# ATOL_MAIN_BOARD_R02A03_20191009.net
KiCad netlist of a schematic drawn in Altium Designer
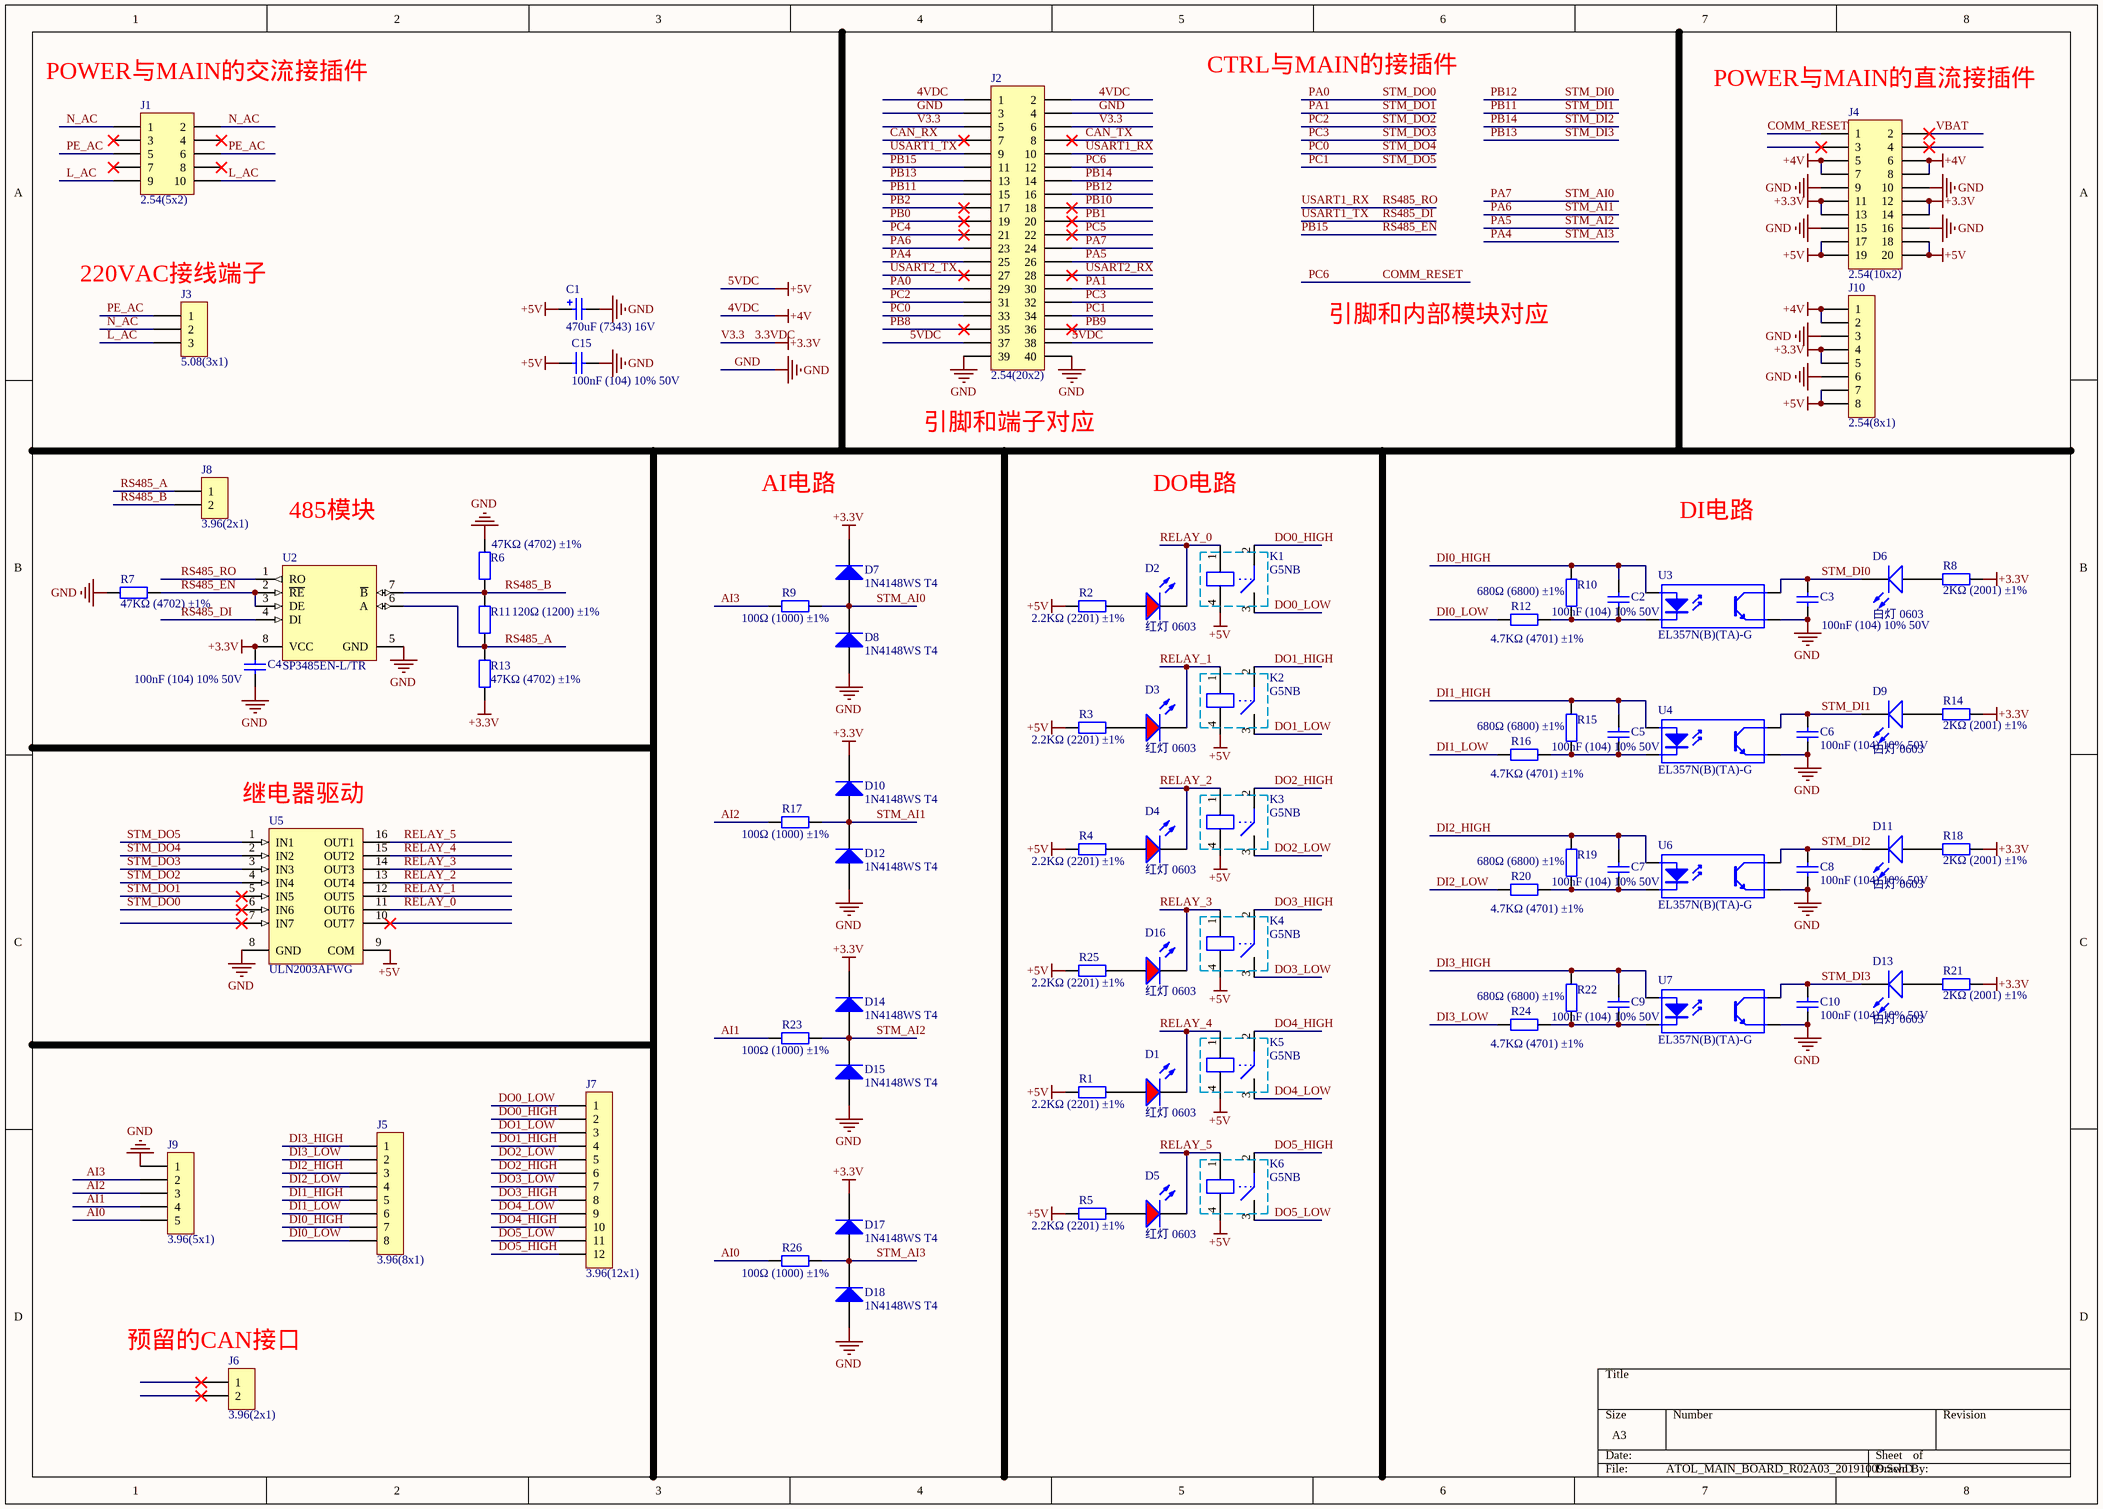
[diagram p0: ATOL_MAIN_BOARD_R02A03_20191009.SchDoc]

(export (version "E")
  (design (tool "Eeschema 10.0.6"))
  (components
    (comp (ref "C1")
      (value "470uF (7343) 16V")
      (footprint "STEC_E(7343-43)")
      (description "钽电容")
      (libsource (lib "Miscellaneous Devices LC") (part "3528 100uF (107) 10% 6.3V"))
    )
    (comp (ref "C2")
      (value "100nF (104) 10% 50V")
      (footprint "0603_C")
      (description "贴片电容")
      (libsource (lib "Miscellaneous Devices LC") (part "0603 100nF (104) 10% 50V"))
    )
    (comp (ref "C3")
      (value "100nF (104) 10% 50V")
      (footprint "0603_C")
      (description "贴片电容")
      (libsource (lib "Miscellaneous Devices LC") (part "0603 100nF (104) 10% 50V"))
    )
    (comp (ref "C4")
      (value "100nF (104) 10% 50V")
      (footprint "0603_C")
      (description "贴片电容")
      (libsource (lib "Miscellaneous Devices LC") (part "0603 100nF (104) 10% 50V"))
    )
    (comp (ref "C5")
      (value "100nF (104) 10% 50V")
      (footprint "0603_C")
      (description "贴片电容")
      (libsource (lib "Miscellaneous Devices LC") (part "0603 100nF (104) 10% 50V"))
    )
    (comp (ref "C6")
      (value "100nF (104) 10% 50V")
      (footprint "0603_C")
      (description "贴片电容")
      (libsource (lib "Miscellaneous Devices LC") (part "0603 100nF (104) 10% 50V"))
    )
    (comp (ref "C7")
      (value "100nF (104) 10% 50V")
      (footprint "0603_C")
      (description "贴片电容")
      (libsource (lib "Miscellaneous Devices LC") (part "0603 100nF (104) 10% 50V"))
    )
    (comp (ref "C8")
      (value "100nF (104) 10% 50V")
      (footprint "0603_C")
      (description "贴片电容")
      (libsource (lib "Miscellaneous Devices LC") (part "0603 100nF (104) 10% 50V"))
    )
    (comp (ref "C9")
      (value "100nF (104) 10% 50V")
      (footprint "0603_C")
      (description "贴片电容")
      (libsource (lib "Miscellaneous Devices LC") (part "0603 100nF (104) 10% 50V"))
    )
    (comp (ref "C10")
      (value "100nF (104) 10% 50V")
      (footprint "0603_C")
      (description "贴片电容")
      (libsource (lib "Miscellaneous Devices LC") (part "0603 100nF (104) 10% 50V"))
    )
    (comp (ref "C15")
      (value "100nF (104) 10% 50V")
      (footprint "0603_C")
      (description "贴片电容")
      (libsource (lib "Miscellaneous Devices LC") (part "0603 100nF (104) 10% 50V"))
    )
    (comp (ref "D1")
      (value "红灯 0603")
      (footprint "0603_LED_S1")
      (description "发光二极管")
      (libsource (lib "Miscellaneous Devices LC") (part "0603 红灯"))
    )
    (comp (ref "D2")
      (value "红灯 0603")
      (footprint "0603_LED_S1")
      (description "发光二极管")
      (libsource (lib "Miscellaneous Devices LC") (part "0603 红灯"))
    )
    (comp (ref "D3")
      (value "红灯 0603")
      (footprint "0603_LED_S1")
      (description "发光二极管")
      (libsource (lib "Miscellaneous Devices LC") (part "0603 红灯"))
    )
    (comp (ref "D4")
      (value "红灯 0603")
      (footprint "0603_LED_S1")
      (description "发光二极管")
      (libsource (lib "Miscellaneous Devices LC") (part "0603 红灯"))
    )
    (comp (ref "D5")
      (value "红灯 0603")
      (footprint "0603_LED_S1")
      (description "发光二极管")
      (libsource (lib "Miscellaneous Devices LC") (part "0603 红灯"))
    )
    (comp (ref "D6")
      (value "白灯 0603")
      (footprint "0603_LED_S1")
      (description "发光二极管")
      (libsource (lib "Miscellaneous Devices LC") (part "0603 白灯"))
    )
    (comp (ref "D7")
      (value "1N4148WS T4")
      (footprint "SOD-323")
      (description "二极管")
      (libsource (lib "Miscellaneous Devices LC") (part "SOD-323 1N4148WS T4"))
    )
    (comp (ref "D8")
      (value "1N4148WS T4")
      (footprint "SOD-323")
      (description "二极管")
      (libsource (lib "Miscellaneous Devices LC") (part "SOD-323 1N4148WS T4"))
    )
    (comp (ref "D9")
      (value "白灯 0603")
      (footprint "0603_LED_S1")
      (description "发光二极管")
      (libsource (lib "Miscellaneous Devices LC") (part "0603 白灯"))
    )
    (comp (ref "D10")
      (value "1N4148WS T4")
      (footprint "SOD-323")
      (description "二极管")
      (libsource (lib "Miscellaneous Devices LC") (part "SOD-323 1N4148WS T4"))
    )
    (comp (ref "D11")
      (value "白灯 0603")
      (footprint "0603_LED_S1")
      (description "发光二极管")
      (libsource (lib "Miscellaneous Devices LC") (part "0603 白灯"))
    )
    (comp (ref "D12")
      (value "1N4148WS T4")
      (footprint "SOD-323")
      (description "二极管")
      (libsource (lib "Miscellaneous Devices LC") (part "SOD-323 1N4148WS T4"))
    )
    (comp (ref "D13")
      (value "白灯 0603")
      (footprint "0603_LED_S1")
      (description "发光二极管")
      (libsource (lib "Miscellaneous Devices LC") (part "0603 白灯"))
    )
    (comp (ref "D14")
      (value "1N4148WS T4")
      (footprint "SOD-323")
      (description "二极管")
      (libsource (lib "Miscellaneous Devices LC") (part "SOD-323 1N4148WS T4"))
    )
    (comp (ref "D15")
      (value "1N4148WS T4")
      (footprint "SOD-323")
      (description "二极管")
      (libsource (lib "Miscellaneous Devices LC") (part "SOD-323 1N4148WS T4"))
    )
    (comp (ref "D16")
      (value "红灯 0603")
      (footprint "0603_LED_S1")
      (description "发光二极管")
      (libsource (lib "Miscellaneous Devices LC") (part "0603 红灯"))
    )
    (comp (ref "D17")
      (value "1N4148WS T4")
      (footprint "SOD-323")
      (description "二极管")
      (libsource (lib "Miscellaneous Devices LC") (part "SOD-323 1N4148WS T4"))
    )
    (comp (ref "D18")
      (value "1N4148WS T4")
      (footprint "SOD-323")
      (description "二极管")
      (libsource (lib "Miscellaneous Devices LC") (part "SOD-323 1N4148WS T4"))
    )
    (comp (ref "J1")
      (value "2.54(5x2)")
      (footprint "DB2.54(5x2)")
      (description "2.54端子")
      (libsource (lib "connector") (part "2.54(5x2)"))
    )
    (comp (ref "J2")
      (value "2.54(20x2)")
      (footprint "DB2.54(20x2)")
      (description "2.54端子")
      (libsource (lib "connector") (part "2.54(20x2)"))
    )
    (comp (ref "J3")
      (value "5.08(3x1)")
      (footprint "KF2EDGK5.08-WI-3P")
      (description "5.08端子")
      (libsource (lib "connector") (part "5.08(3x1)"))
    )
    (comp (ref "J4")
      (value "2.54(10x2)")
      (footprint "DB2.54(10x2)")
      (description "2.54端子")
      (libsource (lib "connector") (part "2.54(10x2)"))
    )
    (comp (ref "J5")
      (value "3.96(8x1)")
      (footprint "HT3.96-WI-8P")
      (description "3.96端子")
      (libsource (lib "connector") (part "3.96(8x1)"))
    )
    (comp (ref "J6")
      (value "3.96(2x1)")
      (footprint "HT3.96-WI-2P")
      (description "3.96端子")
      (libsource (lib "connector") (part "3.96(2x1)"))
    )
    (comp (ref "J7")
      (value "3.96(12x1)")
      (footprint "HT3.96-WI-12P")
      (description "3.96端子")
      (libsource (lib "connector") (part "3.96(12x1)"))
    )
    (comp (ref "J8")
      (value "3.96(2x1)")
      (footprint "HT3.96-WI-2P")
      (description "3.96端子")
      (libsource (lib "connector") (part "3.96(2x1)"))
    )
    (comp (ref "J9")
      (value "3.96(5x1)")
      (footprint "HT3.96-WI-5P")
      (description "3.96端子")
      (libsource (lib "connector") (part "3.96(5x1)"))
    )
    (comp (ref "J10")
      (value "2.54(8x1)")
      (footprint "DB2.54(8x1)")
      (description "2.54端子")
      (libsource (lib "connector") (part "2.54(8x1)"))
    )
    (comp (ref "K1")
      (value "G5NB")
      (footprint "G5NG")
      (description "G5NB/12V/16mA/720R")
      (libsource (lib "ATOL_CHIP") (part "G5NB"))
    )
    (comp (ref "K2")
      (value "G5NB")
      (footprint "G5NG")
      (description "G5NB/12V/16mA/720R")
      (libsource (lib "ATOL_CHIP") (part "G5NB"))
    )
    (comp (ref "K3")
      (value "G5NB")
      (footprint "G5NG")
      (description "G5NB/12V/16mA/720R")
      (libsource (lib "ATOL_CHIP") (part "G5NB"))
    )
    (comp (ref "K4")
      (value "G5NB")
      (footprint "G5NG")
      (description "G5NB/12V/16mA/720R")
      (libsource (lib "ATOL_CHIP") (part "G5NB"))
    )
    (comp (ref "K5")
      (value "G5NB")
      (footprint "G5NG")
      (description "G5NB/12V/16mA/720R")
      (libsource (lib "ATOL_CHIP") (part "G5NB"))
    )
    (comp (ref "K6")
      (value "G5NB")
      (footprint "G5NG")
      (description "G5NB/12V/16mA/720R")
      (libsource (lib "ATOL_CHIP") (part "G5NB"))
    )
    (comp (ref "R1")
      (value "2.2KΩ (2201) ±1%")
      (footprint "0603_R")
      (description "贴片电阻")
      (libsource (lib "Miscellaneous Devices LC") (part "0603 2.2KΩ (2201) 1%"))
    )
    (comp (ref "R2")
      (value "2.2KΩ (2201) ±1%")
      (footprint "0603_R")
      (description "贴片电阻")
      (libsource (lib "Miscellaneous Devices LC") (part "0603 2.2KΩ (2201) 1%"))
    )
    (comp (ref "R3")
      (value "2.2KΩ (2201) ±1%")
      (footprint "0603_R")
      (description "贴片电阻")
      (libsource (lib "Miscellaneous Devices LC") (part "0603 2.2KΩ (2201) 1%"))
    )
    (comp (ref "R4")
      (value "2.2KΩ (2201) ±1%")
      (footprint "0603_R")
      (description "贴片电阻")
      (libsource (lib "Miscellaneous Devices LC") (part "0603 2.2KΩ (2201) 1%"))
    )
    (comp (ref "R5")
      (value "2.2KΩ (2201) ±1%")
      (footprint "0603_R")
      (description "贴片电阻")
      (libsource (lib "Miscellaneous Devices LC") (part "0603 2.2KΩ (2201) 1%"))
    )
    (comp (ref "R6")
      (value "47KΩ (4702) ±1%")
      (footprint "0603_R")
      (description "贴片电阻")
      (libsource (lib "Miscellaneous Devices LC") (part "0603 47KΩ (4702) 1%"))
    )
    (comp (ref "R7")
      (value "47KΩ (4702) ±1%")
      (footprint "0603_R")
      (description "贴片电阻")
      (libsource (lib "") (part "0603 47KΩ (4702) 1%_1"))
    )
    (comp (ref "R8")
      (value "2KΩ (2001) ±1%")
      (footprint "0603_R")
      (description "贴片电阻")
      (libsource (lib "Miscellaneous Devices LC") (part "0603 2KΩ (2001) 1%"))
    )
    (comp (ref "R9")
      (value "100Ω (1000) ±1%")
      (footprint "0603_R")
      (description "贴片电阻")
      (libsource (lib "Miscellaneous Devices LC") (part "0603 100Ω (1000) 1%"))
    )
    (comp (ref "R10")
      (value "680Ω (6800) ±1%")
      (footprint "0603_R")
      (description "贴片电阻")
      (libsource (lib "Miscellaneous Devices LC") (part "0603 680Ω (6800) 1%"))
    )
    (comp (ref "R11")
      (value "120Ω (1200) ±1%")
      (footprint "0603_R")
      (description "贴片电阻")
      (libsource (lib "Miscellaneous Devices LC") (part "0603 120Ω (1200) 1%"))
    )
    (comp (ref "R12")
      (value "4.7KΩ (4701) ±1%")
      (footprint "0603_R")
      (description "贴片电阻")
      (libsource (lib "Miscellaneous Devices LC") (part "0603 4.7KΩ (4701) 1%"))
    )
    (comp (ref "R13")
      (value "47KΩ (4702) ±1%")
      (footprint "0603_R")
      (description "贴片电阻")
      (libsource (lib "Miscellaneous Devices LC") (part "0603 47KΩ (4702) 1%"))
    )
    (comp (ref "R14")
      (value "2KΩ (2001) ±1%")
      (footprint "0603_R")
      (description "贴片电阻")
      (libsource (lib "Miscellaneous Devices LC") (part "0603 2KΩ (2001) 1%"))
    )
    (comp (ref "R15")
      (value "680Ω (6800) ±1%")
      (footprint "0603_R")
      (description "贴片电阻")
      (libsource (lib "Miscellaneous Devices LC") (part "0603 680Ω (6800) 1%"))
    )
    (comp (ref "R16")
      (value "4.7KΩ (4701) ±1%")
      (footprint "0603_R")
      (description "贴片电阻")
      (libsource (lib "Miscellaneous Devices LC") (part "0603 4.7KΩ (4701) 1%"))
    )
    (comp (ref "R17")
      (value "100Ω (1000) ±1%")
      (footprint "0603_R")
      (description "贴片电阻")
      (libsource (lib "Miscellaneous Devices LC") (part "0603 100Ω (1000) 1%"))
    )
    (comp (ref "R18")
      (value "2KΩ (2001) ±1%")
      (footprint "0603_R")
      (description "贴片电阻")
      (libsource (lib "Miscellaneous Devices LC") (part "0603 2KΩ (2001) 1%"))
    )
    (comp (ref "R19")
      (value "680Ω (6800) ±1%")
      (footprint "0603_R")
      (description "贴片电阻")
      (libsource (lib "Miscellaneous Devices LC") (part "0603 680Ω (6800) 1%"))
    )
    (comp (ref "R20")
      (value "4.7KΩ (4701) ±1%")
      (footprint "0603_R")
      (description "贴片电阻")
      (libsource (lib "Miscellaneous Devices LC") (part "0603 4.7KΩ (4701) 1%"))
    )
    (comp (ref "R21")
      (value "2KΩ (2001) ±1%")
      (footprint "0603_R")
      (description "贴片电阻")
      (libsource (lib "Miscellaneous Devices LC") (part "0603 2KΩ (2001) 1%"))
    )
    (comp (ref "R22")
      (value "680Ω (6800) ±1%")
      (footprint "0603_R")
      (description "贴片电阻")
      (libsource (lib "Miscellaneous Devices LC") (part "0603 680Ω (6800) 1%"))
    )
    (comp (ref "R23")
      (value "100Ω (1000) ±1%")
      (footprint "0603_R")
      (description "贴片电阻")
      (libsource (lib "Miscellaneous Devices LC") (part "0603 100Ω (1000) 1%"))
    )
    (comp (ref "R24")
      (value "4.7KΩ (4701) ±1%")
      (footprint "0603_R")
      (description "贴片电阻")
      (libsource (lib "Miscellaneous Devices LC") (part "0603 4.7KΩ (4701) 1%"))
    )
    (comp (ref "R25")
      (value "2.2KΩ (2201) ±1%")
      (footprint "0603_R")
      (description "贴片电阻")
      (libsource (lib "Miscellaneous Devices LC") (part "0603 2.2KΩ (2201) 1%"))
    )
    (comp (ref "R26")
      (value "100Ω (1000) ±1%")
      (footprint "0603_R")
      (description "贴片电阻")
      (libsource (lib "Miscellaneous Devices LC") (part "0603 100Ω (1000) 1%"))
    )
    (comp (ref "U2")
      (value "SP3485EN-L/TR")
      (footprint "SOIC-8_150mil")
      (description "RS-485/RS-422")
      (libsource (lib "Miscellaneous Devices LC") (part "SP3485EN-L/TR_[C8963]"))
    )
    (comp (ref "U3")
      (value "EL357N(B)(TA)-G")
      (footprint "SOP-4_P2.54")
      (description "贴片光耦")
      (libsource (lib "Miscellaneous Devices LC") (part "EL357N(B)(TA)-G_[C6649]"))
    )
    (comp (ref "U4")
      (value "EL357N(B)(TA)-G")
      (footprint "SOP-4_P2.54")
      (description "贴片光耦")
      (libsource (lib "Miscellaneous Devices LC") (part "EL357N(B)(TA)-G_[C6649]"))
    )
    (comp (ref "U5")
      (value "ULN2003AFWG")
      (footprint "SOIC-16_150mil")
      (description "大电流驱动")
      (libsource (lib "Miscellaneous Devices LC") (part "ULN2003AFWG_[C5437]"))
    )
    (comp (ref "U6")
      (value "EL357N(B)(TA)-G")
      (footprint "SOP-4_P2.54")
      (description "贴片光耦")
      (libsource (lib "Miscellaneous Devices LC") (part "EL357N(B)(TA)-G_[C6649]"))
    )
    (comp (ref "U7")
      (value "EL357N(B)(TA)-G")
      (footprint "SOP-4_P2.54")
      (description "贴片光耦")
      (libsource (lib "Miscellaneous Devices LC") (part "EL357N(B)(TA)-G_[C6649]"))
    )
  )
  (nets
    (net (code "1") (name "+3.3V") (class "Default")
      (node (ref "C4") (pin "1") (pinfunction "1_1") (pintype "passive"))
      (node (ref "D10") (pin "2") (pinfunction "K_2") (pintype "passive"))
      (node (ref "D14") (pin "2") (pinfunction "K_2") (pintype "passive"))
      (node (ref "D17") (pin "2") (pinfunction "K_2") (pintype "passive"))
      (node (ref "D7") (pin "2") (pinfunction "K_2") (pintype "passive"))
      (node (ref "J10") (pin "4") (pinfunction "4_4") (pintype "passive"))
      (node (ref "J10") (pin "5") (pinfunction "5_5") (pintype "passive"))
      (node (ref "J2") (pin "5") (pinfunction "5_5") (pintype "passive"))
      (node (ref "J2") (pin "6") (pinfunction "6_6") (pintype "passive"))
      (node (ref "J4") (pin "11") (pinfunction "11_11") (pintype "passive"))
      (node (ref "J4") (pin "12") (pinfunction "12_12") (pintype "passive"))
      (node (ref "J4") (pin "13") (pinfunction "13_13") (pintype "passive"))
      (node (ref "J4") (pin "14") (pinfunction "14_14") (pintype "passive"))
      (node (ref "R13") (pin "1") (pinfunction "1_1") (pintype "passive"))
      (node (ref "R14") (pin "2") (pinfunction "2_2") (pintype "passive"))
      (node (ref "R18") (pin "2") (pinfunction "2_2") (pintype "passive"))
      (node (ref "R21") (pin "2") (pinfunction "2_2") (pintype "passive"))
      (node (ref "R8") (pin "2") (pinfunction "2_2") (pintype "passive"))
      (node (ref "U2") (pin "8") (pinfunction "VCC_8") (pintype "power_in"))
    )
    (net (code "2") (name "+4V") (class "Default")
      (node (ref "J10") (pin "1") (pinfunction "1_1") (pintype "passive"))
      (node (ref "J10") (pin "2") (pinfunction "2_2") (pintype "passive"))
      (node (ref "J2") (pin "1") (pinfunction "1_1") (pintype "passive"))
      (node (ref "J2") (pin "2") (pinfunction "2_2") (pintype "passive"))
      (node (ref "J4") (pin "5") (pinfunction "5_5") (pintype "passive"))
      (node (ref "J4") (pin "6") (pinfunction "6_6") (pintype "passive"))
      (node (ref "J4") (pin "7") (pinfunction "7_7") (pintype "passive"))
      (node (ref "J4") (pin "8") (pinfunction "8_8") (pintype "passive"))
    )
    (net (code "3") (name "+5V") (class "Default")
      (node (ref "C1") (pin "1") (pinfunction "1_1") (pintype "passive"))
      (node (ref "C15") (pin "1") (pinfunction "1_1") (pintype "passive"))
      (node (ref "J10") (pin "7") (pinfunction "7_7") (pintype "passive"))
      (node (ref "J10") (pin "8") (pinfunction "8_8") (pintype "passive"))
      (node (ref "J2") (pin "37") (pinfunction "37_37") (pintype "passive"))
      (node (ref "J2") (pin "38") (pinfunction "38_38") (pintype "passive"))
      (node (ref "J4") (pin "17") (pinfunction "17_17") (pintype "passive"))
      (node (ref "J4") (pin "18") (pinfunction "18_18") (pintype "passive"))
      (node (ref "J4") (pin "19") (pinfunction "19_19") (pintype "passive"))
      (node (ref "J4") (pin "20") (pinfunction "20_20") (pintype "passive"))
      (node (ref "K1") (pin "4") (pinfunction "4_4") (pintype "passive"))
      (node (ref "K2") (pin "4") (pinfunction "4_4") (pintype "passive"))
      (node (ref "K3") (pin "4") (pinfunction "4_4") (pintype "passive"))
      (node (ref "K4") (pin "4") (pinfunction "4_4") (pintype "passive"))
      (node (ref "K5") (pin "4") (pinfunction "4_4") (pintype "passive"))
      (node (ref "K6") (pin "4") (pinfunction "4_4") (pintype "passive"))
      (node (ref "R1") (pin "1") (pinfunction "1_1") (pintype "passive"))
      (node (ref "R2") (pin "1") (pinfunction "1_1") (pintype "passive"))
      (node (ref "R25") (pin "1") (pinfunction "1_1") (pintype "passive"))
      (node (ref "R3") (pin "1") (pinfunction "1_1") (pintype "passive"))
      (node (ref "R4") (pin "1") (pinfunction "1_1") (pintype "passive"))
      (node (ref "R5") (pin "1") (pinfunction "1_1") (pintype "passive"))
      (node (ref "U5") (pin "9") (pinfunction "COM_9") (pintype "passive"))
    )
    (net (code "4") (name "/AI0") (class "Default")
      (node (ref "J9") (pin "5") (pinfunction "5_5") (pintype "passive"))
      (node (ref "R26") (pin "1") (pinfunction "1_1") (pintype "passive"))
    )
    (net (code "5") (name "/AI1") (class "Default")
      (node (ref "J9") (pin "4") (pinfunction "4_4") (pintype "passive"))
      (node (ref "R23") (pin "1") (pinfunction "1_1") (pintype "passive"))
    )
    (net (code "6") (name "/AI2") (class "Default")
      (node (ref "J9") (pin "3") (pinfunction "3_3") (pintype "passive"))
      (node (ref "R17") (pin "1") (pinfunction "1_1") (pintype "passive"))
    )
    (net (code "7") (name "/AI3") (class "Default")
      (node (ref "J9") (pin "2") (pinfunction "2_2") (pintype "passive"))
      (node (ref "R9") (pin "1") (pinfunction "1_1") (pintype "passive"))
    )
    (net (code "8") (name "/CAN_RX") (class "Default")
      (node (ref "J2") (pin "7") (pinfunction "7_7") (pintype "passive+no_connect"))
    )
    (net (code "9") (name "/CAN_TX") (class "Default")
      (node (ref "J2") (pin "8") (pinfunction "8_8") (pintype "passive+no_connect"))
    )
    (net (code "10") (name "/COMM_RESET") (class "Default")
      (node (ref "J2") (pin "12") (pinfunction "12_12") (pintype "passive"))
      (node (ref "J4") (pin "1") (pinfunction "1_1") (pintype "passive"))
    )
    (net (code "11") (name "/DI0_HIGH") (class "Default")
      (node (ref "C2") (pin "2") (pinfunction "2_2") (pintype "passive"))
      (node (ref "J5") (pin "7") (pinfunction "7_7") (pintype "passive"))
      (node (ref "R10") (pin "1") (pinfunction "1_1") (pintype "passive"))
      (node (ref "U3") (pin "1") (pinfunction "A_1") (pintype "passive"))
    )
    (net (code "12") (name "/DI0_LOW") (class "Default")
      (node (ref "J5") (pin "8") (pinfunction "8_8") (pintype "passive"))
      (node (ref "R12") (pin "2") (pinfunction "2_2") (pintype "passive"))
    )
    (net (code "13") (name "/DI1_HIGH") (class "Default")
      (node (ref "C5") (pin "2") (pinfunction "2_2") (pintype "passive"))
      (node (ref "J5") (pin "5") (pinfunction "5_5") (pintype "passive"))
      (node (ref "R15") (pin "1") (pinfunction "1_1") (pintype "passive"))
      (node (ref "U4") (pin "1") (pinfunction "A_1") (pintype "passive"))
    )
    (net (code "14") (name "/DI1_LOW") (class "Default")
      (node (ref "J5") (pin "6") (pinfunction "6_6") (pintype "passive"))
      (node (ref "R16") (pin "2") (pinfunction "2_2") (pintype "passive"))
    )
    (net (code "15") (name "/DI2_HIGH") (class "Default")
      (node (ref "C7") (pin "2") (pinfunction "2_2") (pintype "passive"))
      (node (ref "J5") (pin "3") (pinfunction "3_3") (pintype "passive"))
      (node (ref "R19") (pin "1") (pinfunction "1_1") (pintype "passive"))
      (node (ref "U6") (pin "1") (pinfunction "A_1") (pintype "passive"))
    )
    (net (code "16") (name "/DI2_LOW") (class "Default")
      (node (ref "J5") (pin "4") (pinfunction "4_4") (pintype "passive"))
      (node (ref "R20") (pin "2") (pinfunction "2_2") (pintype "passive"))
    )
    (net (code "17") (name "/DI3_HIGH") (class "Default")
      (node (ref "C9") (pin "2") (pinfunction "2_2") (pintype "passive"))
      (node (ref "J5") (pin "1") (pinfunction "1_1") (pintype "passive"))
      (node (ref "R22") (pin "1") (pinfunction "1_1") (pintype "passive"))
      (node (ref "U7") (pin "1") (pinfunction "A_1") (pintype "passive"))
    )
    (net (code "18") (name "/DI3_LOW") (class "Default")
      (node (ref "J5") (pin "2") (pinfunction "2_2") (pintype "passive"))
      (node (ref "R24") (pin "2") (pinfunction "2_2") (pintype "passive"))
    )
    (net (code "19") (name "/DO0_HIGH") (class "Default")
      (node (ref "J7") (pin "2") (pinfunction "2_2") (pintype "passive"))
      (node (ref "K1") (pin "2") (pinfunction "2_2") (pintype "passive"))
    )
    (net (code "20") (name "/DO0_LOW") (class "Default")
      (node (ref "J7") (pin "1") (pinfunction "1_1") (pintype "passive"))
      (node (ref "K1") (pin "3") (pinfunction "3_3") (pintype "passive"))
    )
    (net (code "21") (name "/DO1_HIGH") (class "Default")
      (node (ref "J7") (pin "4") (pinfunction "4_4") (pintype "passive"))
      (node (ref "K2") (pin "2") (pinfunction "2_2") (pintype "passive"))
    )
    (net (code "22") (name "/DO1_LOW") (class "Default")
      (node (ref "J7") (pin "3") (pinfunction "3_3") (pintype "passive"))
      (node (ref "K2") (pin "3") (pinfunction "3_3") (pintype "passive"))
    )
    (net (code "23") (name "/DO2_HIGH") (class "Default")
      (node (ref "J7") (pin "6") (pinfunction "6_6") (pintype "passive"))
      (node (ref "K3") (pin "2") (pinfunction "2_2") (pintype "passive"))
    )
    (net (code "24") (name "/DO2_LOW") (class "Default")
      (node (ref "J7") (pin "5") (pinfunction "5_5") (pintype "passive"))
      (node (ref "K3") (pin "3") (pinfunction "3_3") (pintype "passive"))
    )
    (net (code "25") (name "/DO3_HIGH") (class "Default")
      (node (ref "J7") (pin "8") (pinfunction "8_8") (pintype "passive"))
      (node (ref "K4") (pin "2") (pinfunction "2_2") (pintype "passive"))
    )
    (net (code "26") (name "/DO3_LOW") (class "Default")
      (node (ref "J7") (pin "7") (pinfunction "7_7") (pintype "passive"))
      (node (ref "K4") (pin "3") (pinfunction "3_3") (pintype "passive"))
    )
    (net (code "27") (name "/DO4_HIGH") (class "Default")
      (node (ref "J7") (pin "10") (pinfunction "10_10") (pintype "passive"))
      (node (ref "K5") (pin "2") (pinfunction "2_2") (pintype "passive"))
    )
    (net (code "28") (name "/DO4_LOW") (class "Default")
      (node (ref "J7") (pin "9") (pinfunction "9_9") (pintype "passive"))
      (node (ref "K5") (pin "3") (pinfunction "3_3") (pintype "passive"))
    )
    (net (code "29") (name "/DO5_HIGH") (class "Default")
      (node (ref "J7") (pin "12") (pinfunction "12_12") (pintype "passive"))
      (node (ref "K6") (pin "2") (pinfunction "2_2") (pintype "passive"))
    )
    (net (code "30") (name "/DO5_LOW") (class "Default")
      (node (ref "J7") (pin "11") (pinfunction "11_11") (pintype "passive"))
      (node (ref "K6") (pin "3") (pinfunction "3_3") (pintype "passive"))
    )
    (net (code "31") (name "/L_AC") (class "Default")
      (node (ref "J1") (pin "10") (pinfunction "10_10") (pintype "passive"))
      (node (ref "J1") (pin "9") (pinfunction "9_9") (pintype "passive"))
      (node (ref "J3") (pin "3") (pinfunction "3_3") (pintype "passive"))
    )
    (net (code "32") (name "/N_AC") (class "Default")
      (node (ref "J1") (pin "1") (pinfunction "1_1") (pintype "passive"))
      (node (ref "J1") (pin "2") (pinfunction "2_2") (pintype "passive"))
      (node (ref "J3") (pin "2") (pinfunction "2_2") (pintype "passive"))
    )
    (net (code "33") (name "/PA0") (class "Default")
      (node (ref "J2") (pin "29") (pinfunction "29_29") (pintype "passive"))
      (node (ref "U5") (pin "6") (pinfunction "IN6_6") (pintype "input"))
    )
    (net (code "34") (name "/PA1") (class "Default")
      (node (ref "J2") (pin "30") (pinfunction "30_30") (pintype "passive"))
      (node (ref "U5") (pin "5") (pinfunction "IN5_5") (pintype "input"))
    )
    (net (code "35") (name "/PA4") (class "Default")
      (node (ref "D17") (pin "1") (pinfunction "A_1") (pintype "passive"))
      (node (ref "D18") (pin "2") (pinfunction "K_2") (pintype "passive"))
      (node (ref "J2") (pin "25") (pinfunction "25_25") (pintype "passive"))
      (node (ref "R26") (pin "2") (pinfunction "2_2") (pintype "passive"))
    )
    (net (code "36") (name "/PA5") (class "Default")
      (node (ref "D14") (pin "1") (pinfunction "A_1") (pintype "passive"))
      (node (ref "D15") (pin "2") (pinfunction "K_2") (pintype "passive"))
      (node (ref "J2") (pin "26") (pinfunction "26_26") (pintype "passive"))
      (node (ref "R23") (pin "2") (pinfunction "2_2") (pintype "passive"))
    )
    (net (code "37") (name "/PA6") (class "Default")
      (node (ref "D10") (pin "1") (pinfunction "A_1") (pintype "passive"))
      (node (ref "D12") (pin "2") (pinfunction "K_2") (pintype "passive"))
      (node (ref "J2") (pin "23") (pinfunction "23_23") (pintype "passive"))
      (node (ref "R17") (pin "2") (pinfunction "2_2") (pintype "passive"))
    )
    (net (code "38") (name "/PA7") (class "Default")
      (node (ref "D7") (pin "1") (pinfunction "A_1") (pintype "passive"))
      (node (ref "D8") (pin "2") (pinfunction "K_2") (pintype "passive"))
      (node (ref "J2") (pin "24") (pinfunction "24_24") (pintype "passive"))
      (node (ref "R9") (pin "2") (pinfunction "2_2") (pintype "passive"))
    )
    (net (code "39") (name "/PB0") (class "Default")
      (node (ref "J2") (pin "19") (pinfunction "19_19") (pintype "passive+no_connect"))
    )
    (net (code "40") (name "/PB1") (class "Default")
      (node (ref "J2") (pin "20") (pinfunction "20_20") (pintype "passive+no_connect"))
    )
    (net (code "41") (name "/PB2") (class "Default")
      (node (ref "J2") (pin "17") (pinfunction "17_17") (pintype "passive+no_connect"))
    )
    (net (code "42") (name "/PB8") (class "Default")
      (node (ref "J2") (pin "35") (pinfunction "35_35") (pintype "passive+no_connect"))
    )
    (net (code "43") (name "/PB9") (class "Default")
      (node (ref "J2") (pin "36") (pinfunction "36_36") (pintype "passive+no_connect"))
    )
    (net (code "44") (name "/PB10") (class "Default")
      (node (ref "J2") (pin "18") (pinfunction "18_18") (pintype "passive+no_connect"))
    )
    (net (code "45") (name "/PB11") (class "Default")
      (node (ref "C6") (pin "2") (pinfunction "2_2") (pintype "passive"))
      (node (ref "D9") (pin "K") (pinfunction "K_K") (pintype "passive"))
      (node (ref "J2") (pin "15") (pinfunction "15_15") (pintype "passive"))
      (node (ref "U4") (pin "4") (pinfunction "C_4") (pintype "passive"))
    )
    (net (code "46") (name "/PB12") (class "Default")
      (node (ref "C3") (pin "2") (pinfunction "2_2") (pintype "passive"))
      (node (ref "D6") (pin "K") (pinfunction "K_K") (pintype "passive"))
      (node (ref "J2") (pin "16") (pinfunction "16_16") (pintype "passive"))
      (node (ref "U3") (pin "4") (pinfunction "C_4") (pintype "passive"))
    )
    (net (code "47") (name "/PB13") (class "Default")
      (node (ref "C10") (pin "2") (pinfunction "2_2") (pintype "passive"))
      (node (ref "D13") (pin "K") (pinfunction "K_K") (pintype "passive"))
      (node (ref "J2") (pin "13") (pinfunction "13_13") (pintype "passive"))
      (node (ref "U7") (pin "4") (pinfunction "C_4") (pintype "passive"))
    )
    (net (code "48") (name "/PB14") (class "Default")
      (node (ref "C8") (pin "2") (pinfunction "2_2") (pintype "passive"))
      (node (ref "D11") (pin "K") (pinfunction "K_K") (pintype "passive"))
      (node (ref "J2") (pin "14") (pinfunction "14_14") (pintype "passive"))
      (node (ref "U6") (pin "4") (pinfunction "C_4") (pintype "passive"))
    )
    (net (code "49") (name "/PB15") (class "Default")
      (node (ref "J2") (pin "11") (pinfunction "11_11") (pintype "passive"))
      (node (ref "R7") (pin "2") (pinfunction "2_2") (pintype "passive"))
      (node (ref "U2") (pin "2") (pinfunction "~{RE}_2") (pintype "input"))
      (node (ref "U2") (pin "3") (pinfunction "DE_3") (pintype "input"))
    )
    (net (code "50") (name "/PC0") (class "Default")
      (node (ref "J2") (pin "33") (pinfunction "33_33") (pintype "passive"))
      (node (ref "U5") (pin "2") (pinfunction "IN2_2") (pintype "input"))
    )
    (net (code "51") (name "/PC1") (class "Default")
      (node (ref "J2") (pin "34") (pinfunction "34_34") (pintype "passive"))
      (node (ref "U5") (pin "1") (pinfunction "IN1_1") (pintype "input"))
    )
    (net (code "52") (name "/PC2") (class "Default")
      (node (ref "J2") (pin "31") (pinfunction "31_31") (pintype "passive"))
      (node (ref "U5") (pin "4") (pinfunction "IN4_4") (pintype "input"))
    )
    (net (code "53") (name "/PC3") (class "Default")
      (node (ref "J2") (pin "32") (pinfunction "32_32") (pintype "passive"))
      (node (ref "U5") (pin "3") (pinfunction "IN3_3") (pintype "input"))
    )
    (net (code "54") (name "/PC4") (class "Default")
      (node (ref "J2") (pin "21") (pinfunction "21_21") (pintype "passive+no_connect"))
    )
    (net (code "55") (name "/PC5") (class "Default")
      (node (ref "J2") (pin "22") (pinfunction "22_22") (pintype "passive+no_connect"))
    )
    (net (code "56") (name "/PE_AC") (class "Default")
      (node (ref "J1") (pin "5") (pinfunction "5_5") (pintype "passive"))
      (node (ref "J1") (pin "6") (pinfunction "6_6") (pintype "passive"))
      (node (ref "J3") (pin "1") (pinfunction "1_1") (pintype "passive"))
    )
    (net (code "57") (name "/RELAY_0") (class "Default")
      (node (ref "D2") (pin "K") (pinfunction "K_K") (pintype "passive"))
      (node (ref "K1") (pin "1") (pinfunction "1_1") (pintype "passive"))
      (node (ref "U5") (pin "11") (pinfunction "OUT6_11") (pintype "open_collector"))
    )
    (net (code "58") (name "/RELAY_1") (class "Default")
      (node (ref "D3") (pin "K") (pinfunction "K_K") (pintype "passive"))
      (node (ref "K2") (pin "1") (pinfunction "1_1") (pintype "passive"))
      (node (ref "U5") (pin "12") (pinfunction "OUT5_12") (pintype "open_collector"))
    )
    (net (code "59") (name "/RELAY_2") (class "Default")
      (node (ref "D4") (pin "K") (pinfunction "K_K") (pintype "passive"))
      (node (ref "K3") (pin "1") (pinfunction "1_1") (pintype "passive"))
      (node (ref "U5") (pin "13") (pinfunction "OUT4_13") (pintype "open_collector"))
    )
    (net (code "60") (name "/RELAY_3") (class "Default")
      (node (ref "D16") (pin "K") (pinfunction "K_K") (pintype "passive"))
      (node (ref "K4") (pin "1") (pinfunction "1_1") (pintype "passive"))
      (node (ref "U5") (pin "14") (pinfunction "OUT3_14") (pintype "open_collector"))
    )
    (net (code "61") (name "/RELAY_4") (class "Default")
      (node (ref "D1") (pin "K") (pinfunction "K_K") (pintype "passive"))
      (node (ref "K5") (pin "1") (pinfunction "1_1") (pintype "passive"))
      (node (ref "U5") (pin "15") (pinfunction "OUT2_15") (pintype "open_collector"))
    )
    (net (code "62") (name "/RELAY_5") (class "Default")
      (node (ref "D5") (pin "K") (pinfunction "K_K") (pintype "passive"))
      (node (ref "K6") (pin "1") (pinfunction "1_1") (pintype "passive"))
      (node (ref "U5") (pin "16") (pinfunction "OUT1_16") (pintype "open_collector"))
    )
    (net (code "63") (name "/RS485_A") (class "Default")
      (node (ref "J8") (pin "1") (pinfunction "1_1") (pintype "passive"))
      (node (ref "R11") (pin "1") (pinfunction "1_1") (pintype "passive"))
      (node (ref "R13") (pin "2") (pinfunction "2_2") (pintype "passive"))
      (node (ref "U2") (pin "6") (pinfunction "A_6") (pintype "bidirectional"))
    )
    (net (code "64") (name "/RS485_B") (class "Default")
      (node (ref "J8") (pin "2") (pinfunction "2_2") (pintype "passive"))
      (node (ref "R11") (pin "2") (pinfunction "2_2") (pintype "passive"))
      (node (ref "R6") (pin "1") (pinfunction "1_1") (pintype "passive"))
      (node (ref "U2") (pin "7") (pinfunction "~{B}_7") (pintype "bidirectional"))
    )
    (net (code "65") (name "/RS485_DI") (class "Default")
      (node (ref "J2") (pin "9") (pinfunction "9_9") (pintype "passive"))
      (node (ref "U2") (pin "4") (pinfunction "DI_4") (pintype "input"))
    )
    (net (code "66") (name "/RS485_RO") (class "Default")
      (node (ref "J2") (pin "10") (pinfunction "10_10") (pintype "passive"))
      (node (ref "U2") (pin "1") (pinfunction "RO_1") (pintype "output"))
    )
    (net (code "67") (name "/USART2_RX") (class "Default")
      (node (ref "J2") (pin "28") (pinfunction "28_28") (pintype "passive+no_connect"))
    )
    (net (code "68") (name "/USART2_TX") (class "Default")
      (node (ref "J2") (pin "27") (pinfunction "27_27") (pintype "passive+no_connect"))
    )
    (net (code "69") (name "/VBAT") (class "Default")
      (node (ref "J4") (pin "2") (pinfunction "2_2") (pintype "passive+no_connect"))
    )
    (net (code "70") (name "GND") (class "Default")
      (node (ref "C1") (pin "2") (pinfunction "2_2") (pintype "passive"))
      (node (ref "C10") (pin "1") (pinfunction "1_1") (pintype "passive"))
      (node (ref "C15") (pin "2") (pinfunction "2_2") (pintype "passive"))
      (node (ref "C3") (pin "1") (pinfunction "1_1") (pintype "passive"))
      (node (ref "C4") (pin "2") (pinfunction "2_2") (pintype "passive"))
      (node (ref "C6") (pin "1") (pinfunction "1_1") (pintype "passive"))
      (node (ref "C8") (pin "1") (pinfunction "1_1") (pintype "passive"))
      (node (ref "D12") (pin "1") (pinfunction "A_1") (pintype "passive"))
      (node (ref "D15") (pin "1") (pinfunction "A_1") (pintype "passive"))
      (node (ref "D18") (pin "1") (pinfunction "A_1") (pintype "passive"))
      (node (ref "D8") (pin "1") (pinfunction "A_1") (pintype "passive"))
      (node (ref "J10") (pin "3") (pinfunction "3_3") (pintype "passive"))
      (node (ref "J10") (pin "6") (pinfunction "6_6") (pintype "passive"))
      (node (ref "J2") (pin "3") (pinfunction "3_3") (pintype "passive"))
      (node (ref "J2") (pin "39") (pinfunction "39_39") (pintype "passive"))
      (node (ref "J2") (pin "4") (pinfunction "4_4") (pintype "passive"))
      (node (ref "J2") (pin "40") (pinfunction "40_40") (pintype "passive"))
      (node (ref "J4") (pin "10") (pinfunction "10_10") (pintype "passive"))
      (node (ref "J4") (pin "15") (pinfunction "15_15") (pintype "passive"))
      (node (ref "J4") (pin "16") (pinfunction "16_16") (pintype "passive"))
      (node (ref "J4") (pin "9") (pinfunction "9_9") (pintype "passive"))
      (node (ref "J9") (pin "1") (pinfunction "1_1") (pintype "passive"))
      (node (ref "R6") (pin "2") (pinfunction "2_2") (pintype "passive"))
      (node (ref "R7") (pin "1") (pinfunction "1_1") (pintype "passive"))
      (node (ref "U2") (pin "5") (pinfunction "GND_5") (pintype "power_in"))
      (node (ref "U3") (pin "3") (pinfunction "E_3") (pintype "passive"))
      (node (ref "U4") (pin "3") (pinfunction "E_3") (pintype "passive"))
      (node (ref "U5") (pin "8") (pinfunction "GND_8") (pintype "power_in"))
      (node (ref "U6") (pin "3") (pinfunction "E_3") (pintype "passive"))
      (node (ref "U7") (pin "3") (pinfunction "E_3") (pintype "passive"))
    )
    (net (code "71") (name "Net-(D1-PadA)") (class "Default")
      (node (ref "D1") (pin "A") (pinfunction "A_A") (pintype "passive"))
      (node (ref "R1") (pin "2") (pinfunction "2_2") (pintype "passive"))
    )
    (net (code "72") (name "Net-(D2-PadA)") (class "Default")
      (node (ref "D2") (pin "A") (pinfunction "A_A") (pintype "passive"))
      (node (ref "R2") (pin "2") (pinfunction "2_2") (pintype "passive"))
    )
    (net (code "73") (name "Net-(D3-PadA)") (class "Default")
      (node (ref "D3") (pin "A") (pinfunction "A_A") (pintype "passive"))
      (node (ref "R3") (pin "2") (pinfunction "2_2") (pintype "passive"))
    )
    (net (code "74") (name "Net-(D4-PadA)") (class "Default")
      (node (ref "D4") (pin "A") (pinfunction "A_A") (pintype "passive"))
      (node (ref "R4") (pin "2") (pinfunction "2_2") (pintype "passive"))
    )
    (net (code "75") (name "Net-(D5-PadA)") (class "Default")
      (node (ref "D5") (pin "A") (pinfunction "A_A") (pintype "passive"))
      (node (ref "R5") (pin "2") (pinfunction "2_2") (pintype "passive"))
    )
    (net (code "76") (name "Net-(D6-PadA)") (class "Default")
      (node (ref "D6") (pin "A") (pinfunction "A_A") (pintype "passive"))
      (node (ref "R8") (pin "1") (pinfunction "1_1") (pintype "passive"))
    )
    (net (code "77") (name "Net-(D9-PadA)") (class "Default")
      (node (ref "D9") (pin "A") (pinfunction "A_A") (pintype "passive"))
      (node (ref "R14") (pin "1") (pinfunction "1_1") (pintype "passive"))
    )
    (net (code "78") (name "Net-(D11-PadA)") (class "Default")
      (node (ref "D11") (pin "A") (pinfunction "A_A") (pintype "passive"))
      (node (ref "R18") (pin "1") (pinfunction "1_1") (pintype "passive"))
    )
    (net (code "79") (name "Net-(D13-PadA)") (class "Default")
      (node (ref "D13") (pin "A") (pinfunction "A_A") (pintype "passive"))
      (node (ref "R21") (pin "1") (pinfunction "1_1") (pintype "passive"))
    )
    (net (code "80") (name "Net-(D16-PadA)") (class "Default")
      (node (ref "D16") (pin "A") (pinfunction "A_A") (pintype "passive"))
      (node (ref "R25") (pin "2") (pinfunction "2_2") (pintype "passive"))
    )
    (net (code "81") (name "Net-(U3-K)") (class "Default")
      (node (ref "C2") (pin "1") (pinfunction "1_1") (pintype "passive"))
      (node (ref "R10") (pin "2") (pinfunction "2_2") (pintype "passive"))
      (node (ref "R12") (pin "1") (pinfunction "1_1") (pintype "passive"))
      (node (ref "U3") (pin "2") (pinfunction "K_2") (pintype "passive"))
    )
    (net (code "82") (name "Net-(U4-K)") (class "Default")
      (node (ref "C5") (pin "1") (pinfunction "1_1") (pintype "passive"))
      (node (ref "R15") (pin "2") (pinfunction "2_2") (pintype "passive"))
      (node (ref "R16") (pin "1") (pinfunction "1_1") (pintype "passive"))
      (node (ref "U4") (pin "2") (pinfunction "K_2") (pintype "passive"))
    )
    (net (code "83") (name "Net-(U6-K)") (class "Default")
      (node (ref "C7") (pin "1") (pinfunction "1_1") (pintype "passive"))
      (node (ref "R19") (pin "2") (pinfunction "2_2") (pintype "passive"))
      (node (ref "R20") (pin "1") (pinfunction "1_1") (pintype "passive"))
      (node (ref "U6") (pin "2") (pinfunction "K_2") (pintype "passive"))
    )
    (net (code "84") (name "Net-(U7-K)") (class "Default")
      (node (ref "C9") (pin "1") (pinfunction "1_1") (pintype "passive"))
      (node (ref "R22") (pin "2") (pinfunction "2_2") (pintype "passive"))
      (node (ref "R24") (pin "1") (pinfunction "1_1") (pintype "passive"))
      (node (ref "U7") (pin "2") (pinfunction "K_2") (pintype "passive"))
    )
    (net (code "85") (name "unconnected-(J1-Pad3)") (class "Default")
      (node (ref "J1") (pin "3") (pinfunction "3_3") (pintype "passive+no_connect"))
    )
    (net (code "86") (name "unconnected-(J1-Pad4)") (class "Default")
      (node (ref "J1") (pin "4") (pinfunction "4_4") (pintype "passive+no_connect"))
    )
    (net (code "87") (name "unconnected-(J1-Pad7)") (class "Default")
      (node (ref "J1") (pin "7") (pinfunction "7_7") (pintype "passive+no_connect"))
    )
    (net (code "88") (name "unconnected-(J1-Pad8)") (class "Default")
      (node (ref "J1") (pin "8") (pinfunction "8_8") (pintype "passive+no_connect"))
    )
    (net (code "89") (name "unconnected-(J4-Pad3)") (class "Default")
      (node (ref "J4") (pin "3") (pinfunction "3_3") (pintype "passive+no_connect"))
    )
    (net (code "90") (name "unconnected-(J4-Pad4)") (class "Default")
      (node (ref "J4") (pin "4") (pinfunction "4_4") (pintype "passive+no_connect"))
    )
    (net (code "91") (name "unconnected-(J6-Pad1)") (class "Default")
      (node (ref "J6") (pin "1") (pinfunction "1_1") (pintype "passive+no_connect"))
    )
    (net (code "92") (name "unconnected-(J6-Pad2)") (class "Default")
      (node (ref "J6") (pin "2") (pinfunction "2_2") (pintype "passive+no_connect"))
    )
    (net (code "93") (name "unconnected-(U5-IN7-Pad7)") (class "Default")
      (node (ref "U5") (pin "7") (pinfunction "IN7_7") (pintype "input+no_connect"))
    )
    (net (code "94") (name "unconnected-(U5-OUT7-Pad10)") (class "Default")
      (node (ref "U5") (pin "10") (pinfunction "OUT7_10") (pintype "open_collector+no_connect"))
    )
  )
)
